# Communication.net
KiCad netlist of a schematic drawn in Altium Designer
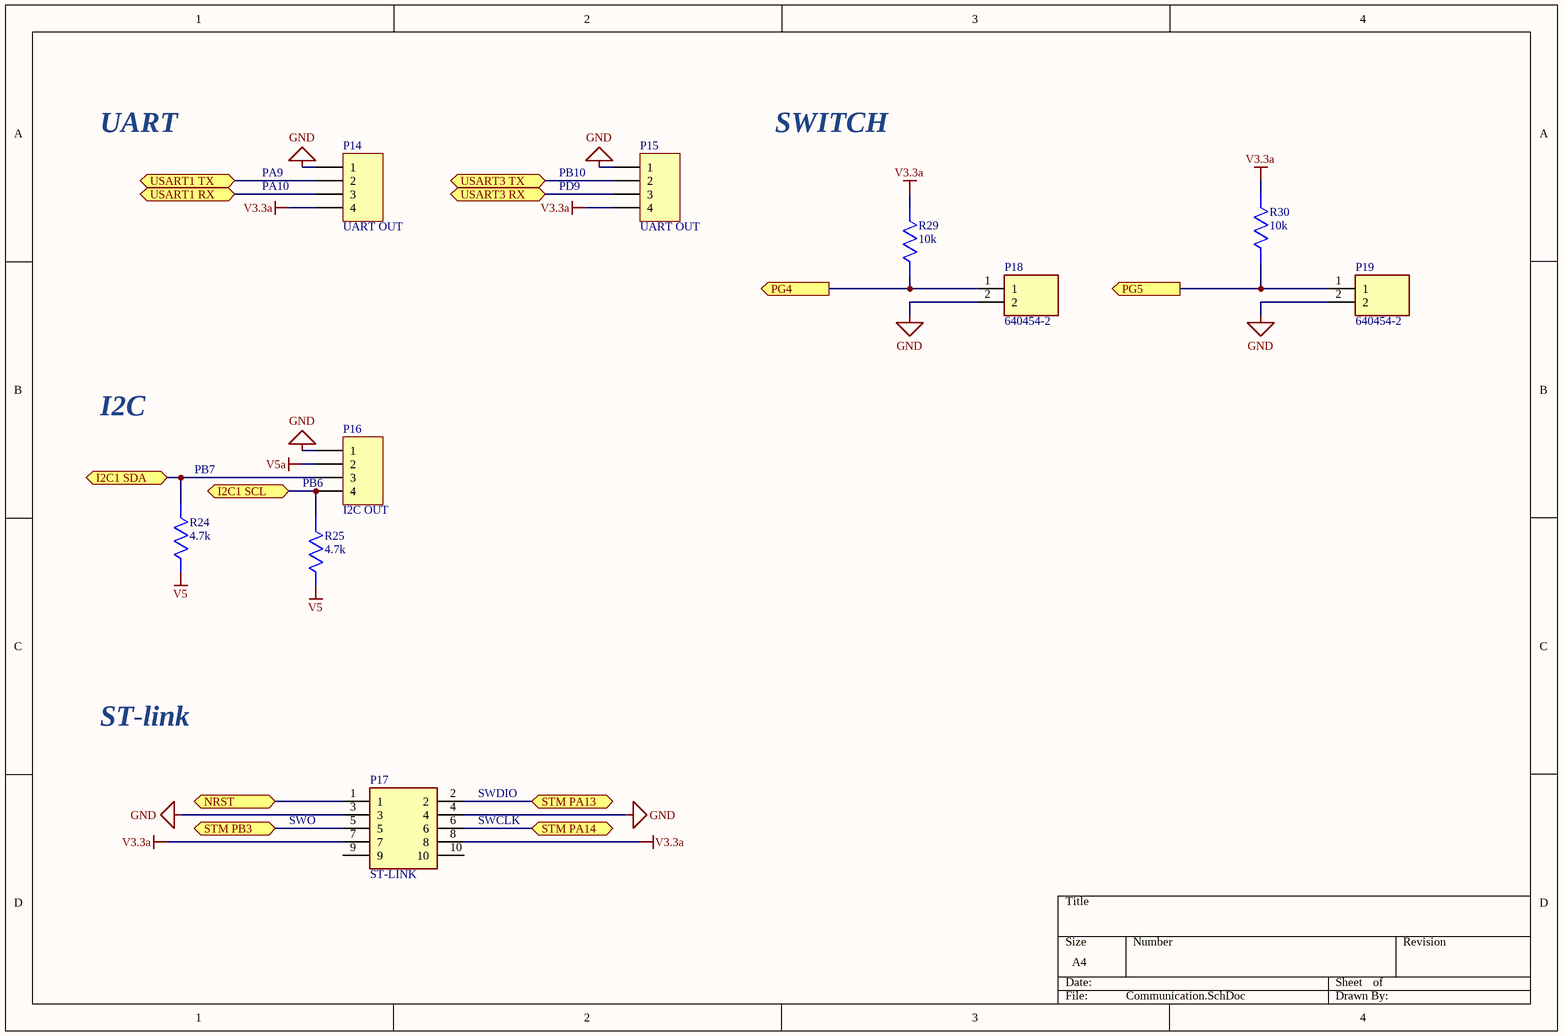
[diagram p0: Communication.SchDoc]

(export (version "E")
  (design (tool "Eeschema 10.0.6"))
  (components
    (comp (ref "P14")
      (value "UART OUT")
      (footprint "HDR1X4")
      (description "Header, 4-Pin")
      (fields (field (name "PUBLISHER") "Altium Limited"))
      (libsource (lib "Miscellaneous Connectors") (part "Header 4"))
    )
    (comp (ref "P15")
      (value "UART OUT")
      (footprint "HDR1X4")
      (description "Header, 4-Pin")
      (fields (field (name "PUBLISHER") "Altium Limited"))
      (libsource (lib "Miscellaneous Connectors") (part "Header 4"))
    )
    (comp (ref "P16")
      (value "I2C OUT")
      (footprint "HDR1X4")
      (description "Header, 4-Pin")
      (fields (field (name "PUBLISHER") "Altium Limited"))
      (libsource (lib "Miscellaneous Connectors") (part "Header 4"))
    )
    (comp (ref "P17")
      (value "ST-LINK")
      (footprint "SamacSys:SHDR10W66P254_2X5_2035X880X920P")
      (description "Connector")
      (fields (field (name "MANUFACTURER_PART_NUMBER") "1-1634688-0"))
      (libsource (lib "*") (part "1-1634688-0"))
    )
    (comp (ref "P18")
      (value "640454-2")
      (footprint "SamacSys:HDRV2W66P0X254_1X2_762X572X1003P")
      (description "Connector")
      (libsource (lib "SamacSys") (part "640454-2"))
    )
    (comp (ref "P19")
      (value "640454-2")
      (footprint "SamacSys:HDRV2W66P0X254_1X2_762X572X1003P")
      (description "Connector")
      (libsource (lib "SamacSys") (part "640454-2"))
    )
    (comp (ref "R24")
      (value "4.7k")
      (footprint "SamacSys:RESC1608X55N")
      (description "Resistor")
      (fields (field (name "MANUFACTURER_PART_NUMBER") "CMP0603-FX-1003ELF"))
      (libsource (lib "SamacSys") (part "CMP0603-FX-1003ELF"))
    )
    (comp (ref "R25")
      (value "4.7k")
      (footprint "SamacSys:RESC1608X55N")
      (description "Resistor")
      (fields (field (name "MANUFACTURER_PART_NUMBER") "CMP0603-FX-1003ELF"))
      (libsource (lib "SamacSys") (part "CMP0603-FX-1003ELF"))
    )
    (comp (ref "R29")
      (value "10k")
      (footprint "SamacSys:RESC1608X55N")
      (description "Resistor")
      (fields (field (name "MANUFACTURER_PART_NUMBER") "CMP0603-FX-1003ELF"))
      (libsource (lib "SamacSys") (part "CMP0603-FX-1003ELF"))
    )
    (comp (ref "R30")
      (value "10k")
      (footprint "SamacSys:RESC1608X55N")
      (description "Resistor")
      (fields (field (name "MANUFACTURER_PART_NUMBER") "CMP0603-FX-1003ELF"))
      (libsource (lib "SamacSys") (part "CMP0603-FX-1003ELF"))
    )
  )
  (nets
    (net (code "1") (name "/I2C1 SCL") (class "Default")
      (node (ref "P16") (pin "4") (pinfunction "4_4") (pintype "passive"))
      (node (ref "R25") (pin "2") (pinfunction "2_2") (pintype "passive"))
    )
    (net (code "2") (name "/I2C1 SDA") (class "Default")
      (node (ref "P16") (pin "3") (pinfunction "3_3") (pintype "passive"))
      (node (ref "R24") (pin "2") (pinfunction "2_2") (pintype "passive"))
    )
    (net (code "3") (name "/NRST") (class "Default")
      (node (ref "P17") (pin "1") (pinfunction "1_1") (pintype "passive"))
    )
    (net (code "4") (name "/PG4") (class "Default")
      (node (ref "P18") (pin "1") (pinfunction "1_1") (pintype "passive"))
      (node (ref "R29") (pin "1") (pinfunction "1_1") (pintype "passive"))
    )
    (net (code "5") (name "/PG5") (class "Default")
      (node (ref "P19") (pin "1") (pinfunction "1_1") (pintype "passive"))
      (node (ref "R30") (pin "1") (pinfunction "1_1") (pintype "passive"))
    )
    (net (code "6") (name "/STM PA13") (class "Default")
      (node (ref "P17") (pin "2") (pinfunction "2_2") (pintype "passive"))
    )
    (net (code "7") (name "/STM PA14") (class "Default")
      (node (ref "P17") (pin "6") (pinfunction "6_6") (pintype "passive"))
    )
    (net (code "8") (name "/STM PB3") (class "Default")
      (node (ref "P17") (pin "5") (pinfunction "5_5") (pintype "passive"))
    )
    (net (code "9") (name "/USART1 RX") (class "Default")
      (node (ref "P14") (pin "3") (pinfunction "3_3") (pintype "passive"))
    )
    (net (code "10") (name "/USART1 TX") (class "Default")
      (node (ref "P14") (pin "2") (pinfunction "2_2") (pintype "passive"))
    )
    (net (code "11") (name "/USART3 RX") (class "Default")
      (node (ref "P15") (pin "3") (pinfunction "3_3") (pintype "passive"))
    )
    (net (code "12") (name "/USART3 TX") (class "Default")
      (node (ref "P15") (pin "2") (pinfunction "2_2") (pintype "passive"))
    )
    (net (code "13") (name "GND") (class "Default")
      (node (ref "P14") (pin "1") (pinfunction "1_1") (pintype "passive"))
      (node (ref "P15") (pin "1") (pinfunction "1_1") (pintype "passive"))
      (node (ref "P16") (pin "1") (pinfunction "1_1") (pintype "passive"))
      (node (ref "P17") (pin "3") (pinfunction "3_3") (pintype "passive"))
      (node (ref "P17") (pin "4") (pinfunction "4_4") (pintype "passive"))
      (node (ref "P18") (pin "2") (pinfunction "2_2") (pintype "passive"))
      (node (ref "P19") (pin "2") (pinfunction "2_2") (pintype "passive"))
    )
    (net (code "14") (name "V3.3a") (class "Default")
      (node (ref "P14") (pin "4") (pinfunction "4_4") (pintype "passive"))
      (node (ref "P15") (pin "4") (pinfunction "4_4") (pintype "passive"))
      (node (ref "P17") (pin "7") (pinfunction "7_7") (pintype "passive"))
      (node (ref "P17") (pin "8") (pinfunction "8_8") (pintype "passive"))
      (node (ref "R29") (pin "2") (pinfunction "2_2") (pintype "passive"))
      (node (ref "R30") (pin "2") (pinfunction "2_2") (pintype "passive"))
    )
    (net (code "15") (name "V5") (class "Default")
      (node (ref "R24") (pin "1") (pinfunction "1_1") (pintype "passive"))
      (node (ref "R25") (pin "1") (pinfunction "1_1") (pintype "passive"))
    )
    (net (code "16") (name "V5a") (class "Default")
      (node (ref "P16") (pin "2") (pinfunction "2_2") (pintype "passive"))
    )
    (net (code "17") (name "unconnected-(P17-Pad9)") (class "Default")
      (node (ref "P17") (pin "9") (pinfunction "9_9") (pintype "passive"))
    )
    (net (code "18") (name "unconnected-(P17-Pad10)") (class "Default")
      (node (ref "P17") (pin "10") (pinfunction "10_10") (pintype "passive"))
    )
  )
)
